# 19_-CAMERA_PWR_CONNECTORS.net
KiCad netlist of a schematic drawn in Altium Designer
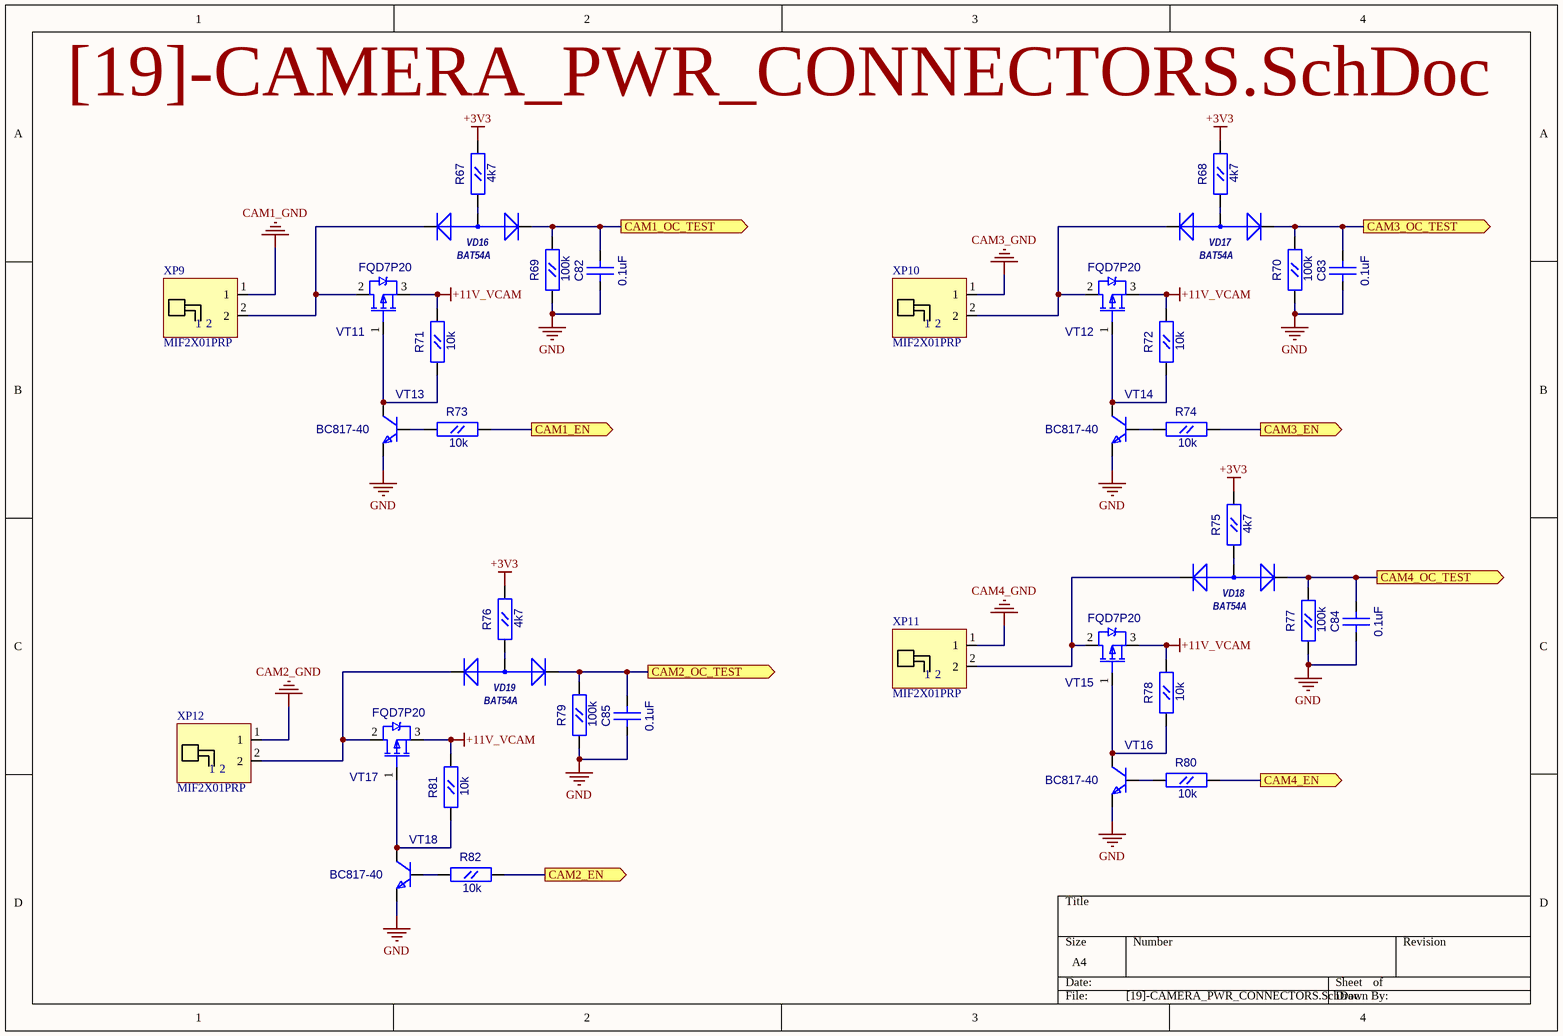
[diagram p0: [19]-CAMERA_PWR_CONNECTORS.SchDoc]

(export (version "E")
  (design (tool "Eeschema 10.0.6"))
  (components
    (comp (ref "C82")
      (value "0.1uF")
      (footprint "CC0603")
      (description "CC0603")
      (libsource (lib "fizik_lib") (part "CC0603"))
    )
    (comp (ref "C83")
      (value "0.1uF")
      (footprint "CC0603")
      (description "CC0603")
      (libsource (lib "fizik_lib") (part "CC0603"))
    )
    (comp (ref "C84")
      (value "0.1uF")
      (footprint "CC0603")
      (description "CC0603")
      (libsource (lib "fizik_lib") (part "CC0603"))
    )
    (comp (ref "C85")
      (value "0.1uF")
      (footprint "CC0603")
      (description "CC0603")
      (libsource (lib "fizik_lib") (part "CC0603"))
    )
    (comp (ref "R67")
      (value "4k7")
      (footprint "RC0603")
      (description "RC0603")
      (libsource (lib "fizik_lib") (part "RC0603"))
    )
    (comp (ref "R68")
      (value "4k7")
      (footprint "RC0603")
      (description "RC0603")
      (libsource (lib "fizik_lib") (part "RC0603"))
    )
    (comp (ref "R69")
      (value "100k")
      (footprint "RC0603")
      (description "RC0603")
      (libsource (lib "fizik_lib") (part "RC0603"))
    )
    (comp (ref "R70")
      (value "100k")
      (footprint "RC0603")
      (description "RC0603")
      (libsource (lib "fizik_lib") (part "RC0603"))
    )
    (comp (ref "R71")
      (value "10k")
      (footprint "RC0603")
      (description "RC0603")
      (libsource (lib "fizik_lib") (part "RC0603"))
    )
    (comp (ref "R72")
      (value "10k")
      (footprint "RC0603")
      (description "RC0603")
      (libsource (lib "fizik_lib") (part "RC0603"))
    )
    (comp (ref "R73")
      (value "10k")
      (footprint "RC0603")
      (description "RC0603")
      (libsource (lib "fizik_lib") (part "RC0603"))
    )
    (comp (ref "R74")
      (value "10k")
      (footprint "RC0603")
      (description "RC0603")
      (libsource (lib "fizik_lib") (part "RC0603"))
    )
    (comp (ref "R75")
      (value "4k7")
      (footprint "RC0603")
      (description "RC0603")
      (libsource (lib "fizik_lib") (part "RC0603"))
    )
    (comp (ref "R76")
      (value "4k7")
      (footprint "RC0603")
      (description "RC0603")
      (libsource (lib "fizik_lib") (part "RC0603"))
    )
    (comp (ref "R77")
      (value "100k")
      (footprint "RC0603")
      (description "RC0603")
      (libsource (lib "fizik_lib") (part "RC0603"))
    )
    (comp (ref "R78")
      (value "10k")
      (footprint "RC0603")
      (description "RC0603")
      (libsource (lib "fizik_lib") (part "RC0603"))
    )
    (comp (ref "R79")
      (value "100k")
      (footprint "RC0603")
      (description "RC0603")
      (libsource (lib "fizik_lib") (part "RC0603"))
    )
    (comp (ref "R80")
      (value "10k")
      (footprint "RC0603")
      (description "RC0603")
      (libsource (lib "fizik_lib") (part "RC0603"))
    )
    (comp (ref "R81")
      (value "10k")
      (footprint "RC0603")
      (description "RC0603")
      (libsource (lib "fizik_lib") (part "RC0603"))
    )
    (comp (ref "R82")
      (value "10k")
      (footprint "RC0603")
      (description "RC0603")
      (libsource (lib "fizik_lib") (part "RC0603"))
    )
    (comp (ref "VD16")
      (value "BAT54A")
      (footprint "SOT-23(123)")
      (description "1.0 Ampere General Purpose Rectifier")
      (libsource (lib "fizik_lib") (part "BAT54A"))
    )
    (comp (ref "VD17")
      (value "BAT54A")
      (footprint "SOT-23(123)")
      (description "1.0 Ampere General Purpose Rectifier")
      (libsource (lib "fizik_lib") (part "BAT54A"))
    )
    (comp (ref "VD18")
      (value "BAT54A")
      (footprint "SOT-23(123)")
      (description "1.0 Ampere General Purpose Rectifier")
      (libsource (lib "fizik_lib") (part "BAT54A"))
    )
    (comp (ref "VD19")
      (value "BAT54A")
      (footprint "SOT-23(123)")
      (description "1.0 Ampere General Purpose Rectifier")
      (libsource (lib "fizik_lib") (part "BAT54A"))
    )
    (comp (ref "VT11")
      (value "FQD7P20")
      (footprint "D-PAK(TO-252AA)")
      (description "HEXFET Power MOSFET")
      (libsource (lib "gprs_modem_2") (part "IRFR9220"))
    )
    (comp (ref "VT12")
      (value "FQD7P20")
      (footprint "D-PAK(TO-252AA)")
      (description "HEXFET Power MOSFET")
      (libsource (lib "gprs_modem_2") (part "IRFR9220"))
    )
    (comp (ref "VT13")
      (value "BC817-40")
      (footprint "SOT-23(123)")
      (description "NPN 500ma transistor")
      (libsource (lib "fizik_lib") (part "BC846BLT1"))
    )
    (comp (ref "VT14")
      (value "BC817-40")
      (footprint "SOT-23(123)")
      (description "NPN 500ma transistor")
      (libsource (lib "fizik_lib") (part "BC846BLT1"))
    )
    (comp (ref "VT15")
      (value "FQD7P20")
      (footprint "D-PAK(TO-252AA)")
      (description "HEXFET Power MOSFET")
      (libsource (lib "gprs_modem_2") (part "IRFR9220"))
    )
    (comp (ref "VT16")
      (value "BC817-40")
      (footprint "SOT-23(123)")
      (description "NPN 500ma transistor")
      (libsource (lib "fizik_lib") (part "BC846BLT1"))
    )
    (comp (ref "VT17")
      (value "FQD7P20")
      (footprint "D-PAK(TO-252AA)")
      (description "HEXFET Power MOSFET")
      (libsource (lib "gprs_modem_2") (part "IRFR9220"))
    )
    (comp (ref "VT18")
      (value "BC817-40")
      (footprint "SOT-23(123)")
      (description "NPN 500ma transistor")
      (libsource (lib "fizik_lib") (part "BC846BLT1"))
    )
    (comp (ref "XP9")
      (value "MIF2X01PRP")
      (footprint "MIF2x01PRP")
      (description "Molex connector 3.0mm pitch")
      (libsource (lib "fizik_lib") (part "MIF2X01PRP"))
    )
    (comp (ref "XP10")
      (value "MIF2X01PRP")
      (footprint "MIF2x01PRP")
      (description "Molex connector 3.0mm pitch")
      (libsource (lib "fizik_lib") (part "MIF2X01PRP"))
    )
    (comp (ref "XP11")
      (value "MIF2X01PRP")
      (footprint "MIF2x01PRP")
      (description "Molex connector 3.0mm pitch")
      (libsource (lib "fizik_lib") (part "MIF2X01PRP"))
    )
    (comp (ref "XP12")
      (value "MIF2X01PRP")
      (footprint "MIF2x01PRP")
      (description "Molex connector 3.0mm pitch")
      (libsource (lib "fizik_lib") (part "MIF2X01PRP"))
    )
  )
  (nets
    (net (code "1") (name "+3V3") (class "Default")
      (node (ref "R67") (pin "2") (pinfunction "B_2") (pintype "passive"))
      (node (ref "R68") (pin "2") (pinfunction "B_2") (pintype "passive"))
      (node (ref "R75") (pin "2") (pinfunction "B_2") (pintype "passive"))
      (node (ref "R76") (pin "2") (pinfunction "B_2") (pintype "passive"))
    )
    (net (code "2") (name "+11V_VCAM") (class "Default")
      (node (ref "R71") (pin "2") (pinfunction "B_2") (pintype "passive"))
      (node (ref "R72") (pin "2") (pinfunction "B_2") (pintype "passive"))
      (node (ref "R78") (pin "2") (pinfunction "B_2") (pintype "passive"))
      (node (ref "R81") (pin "2") (pinfunction "B_2") (pintype "passive"))
      (node (ref "VT11") (pin "3") (pinfunction "S_3") (pintype "passive"))
      (node (ref "VT12") (pin "3") (pinfunction "S_3") (pintype "passive"))
      (node (ref "VT15") (pin "3") (pinfunction "S_3") (pintype "passive"))
      (node (ref "VT17") (pin "3") (pinfunction "S_3") (pintype "passive"))
    )
    (net (code "3") (name "/CAM1_EN") (class "Default")
      (node (ref "R73") (pin "2") (pinfunction "B_2") (pintype "passive"))
    )
    (net (code "4") (name "/CAM1_OC_TEST") (class "Default")
      (node (ref "C82") (pin "2") (pinfunction "B_2") (pintype "passive"))
      (node (ref "R69") (pin "2") (pinfunction "B_2") (pintype "passive"))
      (node (ref "VD16") (pin "2") (pinfunction "K_2") (pintype "passive"))
    )
    (net (code "5") (name "/CAM2_EN") (class "Default")
      (node (ref "R82") (pin "2") (pinfunction "B_2") (pintype "passive"))
    )
    (net (code "6") (name "/CAM2_OC_TEST") (class "Default")
      (node (ref "C85") (pin "2") (pinfunction "B_2") (pintype "passive"))
      (node (ref "R79") (pin "2") (pinfunction "B_2") (pintype "passive"))
      (node (ref "VD19") (pin "2") (pinfunction "K_2") (pintype "passive"))
    )
    (net (code "7") (name "/CAM3_EN") (class "Default")
      (node (ref "R74") (pin "2") (pinfunction "B_2") (pintype "passive"))
    )
    (net (code "8") (name "/CAM3_OC_TEST") (class "Default")
      (node (ref "C83") (pin "2") (pinfunction "B_2") (pintype "passive"))
      (node (ref "R70") (pin "2") (pinfunction "B_2") (pintype "passive"))
      (node (ref "VD17") (pin "2") (pinfunction "K_2") (pintype "passive"))
    )
    (net (code "9") (name "/CAM4_EN") (class "Default")
      (node (ref "R80") (pin "2") (pinfunction "B_2") (pintype "passive"))
    )
    (net (code "10") (name "/CAM4_OC_TEST") (class "Default")
      (node (ref "C84") (pin "2") (pinfunction "B_2") (pintype "passive"))
      (node (ref "R77") (pin "2") (pinfunction "B_2") (pintype "passive"))
      (node (ref "VD18") (pin "2") (pinfunction "K_2") (pintype "passive"))
    )
    (net (code "11") (name "CAM1_GND") (class "Default")
      (node (ref "XP9") (pin "1") (pinfunction "1_1") (pintype "passive"))
    )
    (net (code "12") (name "CAM2_GND") (class "Default")
      (node (ref "XP12") (pin "1") (pinfunction "1_1") (pintype "passive"))
    )
    (net (code "13") (name "CAM3_GND") (class "Default")
      (node (ref "XP10") (pin "1") (pinfunction "1_1") (pintype "passive"))
    )
    (net (code "14") (name "CAM4_GND") (class "Default")
      (node (ref "XP11") (pin "1") (pinfunction "1_1") (pintype "passive"))
    )
    (net (code "15") (name "GND") (class "Default")
      (node (ref "C82") (pin "1") (pinfunction "A_1") (pintype "passive"))
      (node (ref "C83") (pin "1") (pinfunction "A_1") (pintype "passive"))
      (node (ref "C84") (pin "1") (pinfunction "A_1") (pintype "passive"))
      (node (ref "C85") (pin "1") (pinfunction "A_1") (pintype "passive"))
      (node (ref "R69") (pin "1") (pinfunction "A_1") (pintype "passive"))
      (node (ref "R70") (pin "1") (pinfunction "A_1") (pintype "passive"))
      (node (ref "R77") (pin "1") (pinfunction "A_1") (pintype "passive"))
      (node (ref "R79") (pin "1") (pinfunction "A_1") (pintype "passive"))
      (node (ref "VT13") (pin "2") (pinfunction "E_2") (pintype "passive"))
      (node (ref "VT14") (pin "2") (pinfunction "E_2") (pintype "passive"))
      (node (ref "VT16") (pin "2") (pinfunction "E_2") (pintype "passive"))
      (node (ref "VT18") (pin "2") (pinfunction "E_2") (pintype "passive"))
    )
    (net (code "16") (name "Net-(R67-A)") (class "Default")
      (node (ref "R67") (pin "1") (pinfunction "A_1") (pintype "passive"))
      (node (ref "VD16") (pin "3") (pinfunction "A_3") (pintype "passive"))
    )
    (net (code "17") (name "Net-(R68-A)") (class "Default")
      (node (ref "R68") (pin "1") (pinfunction "A_1") (pintype "passive"))
      (node (ref "VD17") (pin "3") (pinfunction "A_3") (pintype "passive"))
    )
    (net (code "18") (name "Net-(R71-A)") (class "Default")
      (node (ref "R71") (pin "1") (pinfunction "A_1") (pintype "passive"))
      (node (ref "VT11") (pin "1") (pinfunction "G_1") (pintype "passive"))
      (node (ref "VT13") (pin "3") (pinfunction "C_3") (pintype "passive"))
    )
    (net (code "19") (name "Net-(R72-A)") (class "Default")
      (node (ref "R72") (pin "1") (pinfunction "A_1") (pintype "passive"))
      (node (ref "VT12") (pin "1") (pinfunction "G_1") (pintype "passive"))
      (node (ref "VT14") (pin "3") (pinfunction "C_3") (pintype "passive"))
    )
    (net (code "20") (name "Net-(R73-A)") (class "Default")
      (node (ref "R73") (pin "1") (pinfunction "A_1") (pintype "passive"))
      (node (ref "VT13") (pin "1") (pinfunction "B_1") (pintype "passive"))
    )
    (net (code "21") (name "Net-(R74-A)") (class "Default")
      (node (ref "R74") (pin "1") (pinfunction "A_1") (pintype "passive"))
      (node (ref "VT14") (pin "1") (pinfunction "B_1") (pintype "passive"))
    )
    (net (code "22") (name "Net-(R75-A)") (class "Default")
      (node (ref "R75") (pin "1") (pinfunction "A_1") (pintype "passive"))
      (node (ref "VD18") (pin "3") (pinfunction "A_3") (pintype "passive"))
    )
    (net (code "23") (name "Net-(R76-A)") (class "Default")
      (node (ref "R76") (pin "1") (pinfunction "A_1") (pintype "passive"))
      (node (ref "VD19") (pin "3") (pinfunction "A_3") (pintype "passive"))
    )
    (net (code "24") (name "Net-(R78-A)") (class "Default")
      (node (ref "R78") (pin "1") (pinfunction "A_1") (pintype "passive"))
      (node (ref "VT15") (pin "1") (pinfunction "G_1") (pintype "passive"))
      (node (ref "VT16") (pin "3") (pinfunction "C_3") (pintype "passive"))
    )
    (net (code "25") (name "Net-(R80-A)") (class "Default")
      (node (ref "R80") (pin "1") (pinfunction "A_1") (pintype "passive"))
      (node (ref "VT16") (pin "1") (pinfunction "B_1") (pintype "passive"))
    )
    (net (code "26") (name "Net-(R81-A)") (class "Default")
      (node (ref "R81") (pin "1") (pinfunction "A_1") (pintype "passive"))
      (node (ref "VT17") (pin "1") (pinfunction "G_1") (pintype "passive"))
      (node (ref "VT18") (pin "3") (pinfunction "C_3") (pintype "passive"))
    )
    (net (code "27") (name "Net-(R82-A)") (class "Default")
      (node (ref "R82") (pin "1") (pinfunction "A_1") (pintype "passive"))
      (node (ref "VT18") (pin "1") (pinfunction "B_1") (pintype "passive"))
    )
    (net (code "28") (name "Net-(VT11-D)") (class "Default")
      (node (ref "VD16") (pin "1") (pinfunction "K_1") (pintype "passive"))
      (node (ref "VT11") (pin "2") (pinfunction "D_2") (pintype "passive"))
      (node (ref "XP9") (pin "2") (pinfunction "2_2") (pintype "passive"))
    )
    (net (code "29") (name "Net-(VT12-D)") (class "Default")
      (node (ref "VD17") (pin "1") (pinfunction "K_1") (pintype "passive"))
      (node (ref "VT12") (pin "2") (pinfunction "D_2") (pintype "passive"))
      (node (ref "XP10") (pin "2") (pinfunction "2_2") (pintype "passive"))
    )
    (net (code "30") (name "Net-(VT15-D)") (class "Default")
      (node (ref "VD18") (pin "1") (pinfunction "K_1") (pintype "passive"))
      (node (ref "VT15") (pin "2") (pinfunction "D_2") (pintype "passive"))
      (node (ref "XP11") (pin "2") (pinfunction "2_2") (pintype "passive"))
    )
    (net (code "31") (name "Net-(VT17-D)") (class "Default")
      (node (ref "VD19") (pin "1") (pinfunction "K_1") (pintype "passive"))
      (node (ref "VT17") (pin "2") (pinfunction "D_2") (pintype "passive"))
      (node (ref "XP12") (pin "2") (pinfunction "2_2") (pintype "passive"))
    )
  )
)
